# TL061invertingamp.net
KiCad netlist of a schematic drawn in Altium Designer
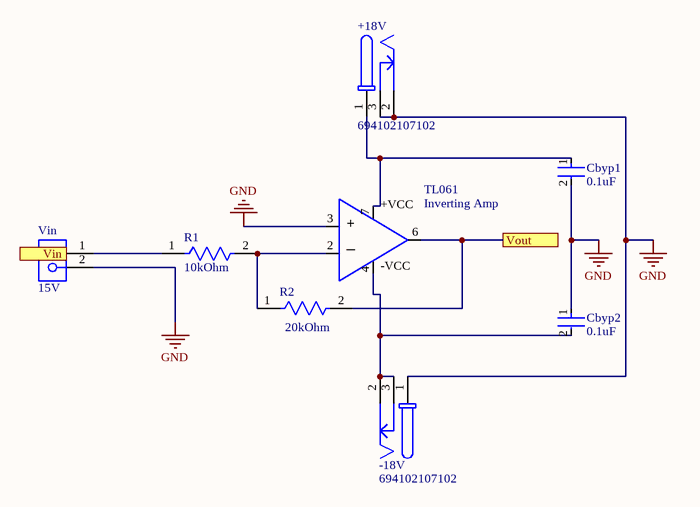
[diagram p0: TL061invertingamp.SchDoc]

(export (version "E")
  (design (tool "Eeschema 10.0.6"))
  (components
    (comp (ref "+18V")
      (value "694102107102")
      (footprint "694102107102")
      (libsource (lib "Altium Content Vault") (part "DC Power Jack"))
    )
    (comp (ref "-18V")
      (value "694102107102")
      (footprint "694102107102")
      (libsource (lib "Altium Content Vault") (part "DC Power Jack"))
    )
    (comp (ref "Cbyp1")
      (value "0.1uF")
      (footprint "FP-CC0402-MFG")
      (description "CAP CER 0.1UF 16V X7R 0402")
      (fields (field (name "MANUFACTURER") "YAGEO") (field (name "TOLERANCE") "0.1"))
      (libsource (lib "Altium Content Vault") (part "11868f565c42a9108669ba33697ecf6"))
    )
    (comp (ref "Cbyp2")
      (value "0.1uF")
      (footprint "FP-CC0402-MFG")
      (description "CAP CER 0.1UF 16V X7R 0402")
      (fields (field (name "MANUFACTURER") "YAGEO") (field (name "TOLERANCE") "0.1"))
      (libsource (lib "Altium Content Vault") (part "11868f565c42a9108669ba33697ecf6"))
    )
    (comp (ref "R1")
      (value "10kOhm")
      (footprint "FP-MBB0207-MFG")
      (description "RES 10K OHM 0.6W 1% AXIAL")
      (fields (field (name "TOLERANCE") "1%"))
      (libsource (lib "Altium Content Vault") (part "1029c3af85768c4190bb7ad29bc67b5"))
    )
    (comp (ref "R2")
      (value "20kOhm")
      (footprint "FP-MRS1600-MFG")
      (description "RES 20K OHM 0.4W 1% AXIAL")
      (fields (field (name "TOLERANCE") "1%"))
      (libsource (lib "Altium Content Vault") (part "1029c3af85768c4190bb7ad29bc67b5"))
    )
    (comp (ref "TL061")
      (value "Inverting Amp")
      (footprint "TLC061ACD")
      (libsource (lib "gsl") (part "TL061ACD"))
    )
    (comp (ref "Vin")
      (value "15V")
      (footprint "691408520002B")
      (description "691408520002B Terminal Block, Wtb, 2WAY, 28-12AWG;")
      (libsource (lib "Altium Content Vault") (part "TBL - 1R - 02P - Female"))
    )
  )
  (nets
    (net (code "2") (name "/Vout") (class "Default")
      (node (ref "R2") (pin "2") (pinfunction "2_2") (pintype "passive"))
      (node (ref "TL061") (pin "6") (pintype "passive"))
    )
    (net (code "3") (name "GND") (class "Default")
      (node (ref "+18V") (pin "2") (pinfunction "2_2") (pintype "passive"))
      (node (ref "+18V") (pin "3") (pinfunction "3_3") (pintype "passive"))
      (node (ref "-18V") (pin "1") (pinfunction "1_1") (pintype "passive"))
      (node (ref "Cbyp1") (pin "2") (pinfunction "2_2") (pintype "passive"))
      (node (ref "Cbyp2") (pin "1") (pinfunction "1_1") (pintype "passive"))
      (node (ref "TL061") (pin "3") (pintype "passive"))
      (node (ref "Vin") (pin "2") (pinfunction "2_2") (pintype "passive"))
    )
    (net (code "4") (name "Net-(+18V-Pad1)") (class "Default")
      (node (ref "+18V") (pin "1") (pinfunction "1_1") (pintype "passive"))
      (node (ref "Cbyp1") (pin "1") (pinfunction "1_1") (pintype "passive"))
      (node (ref "TL061") (pin "7") (pintype "passive"))
    )
    (net (code "5") (name "Net-(-18V-Pad2)") (class "Default")
      (node (ref "-18V") (pin "2") (pinfunction "2_2") (pintype "passive"))
      (node (ref "-18V") (pin "3") (pinfunction "3_3") (pintype "passive"))
      (node (ref "Cbyp2") (pin "2") (pinfunction "2_2") (pintype "passive"))
      (node (ref "TL061") (pin "4") (pintype "passive"))
    )
    (net (code "6") (name "Net-(R1-Pad1)") (class "Default")
      (node (ref "R1") (pin "1") (pinfunction "1_1") (pintype "passive"))
      (node (ref "Vin") (pin "1") (pinfunction "1_1") (pintype "passive"))
    )
    (net (code "7") (name "Net-(R1-Pad2)") (class "Default")
      (node (ref "R1") (pin "2") (pinfunction "2_2") (pintype "passive"))
      (node (ref "R2") (pin "1") (pinfunction "1_1") (pintype "passive"))
      (node (ref "TL061") (pin "2") (pintype "passive"))
    )
  )
)
